# 5_-motor_driver.net
KiCad netlist of a schematic drawn in Altium Designer
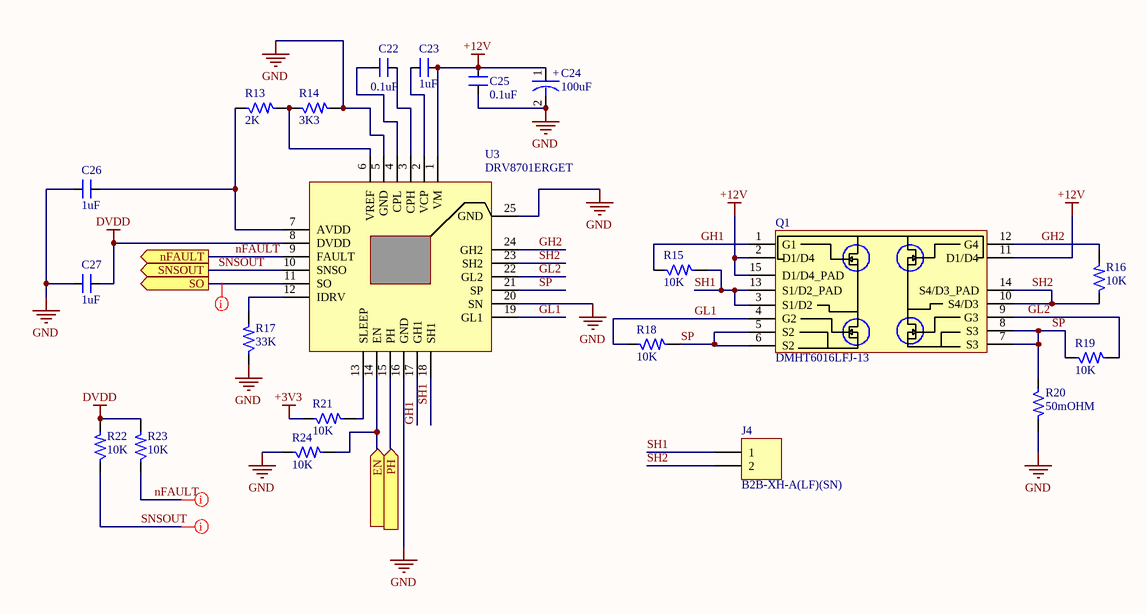
[diagram p0: [5]-motor driver.SchDoc]

(export (version "E")
  (design (tool "Eeschema 10.0.6"))
  (components
    (comp (ref "C22")
      (value "0.1uF")
      (footprint "CAP_0805")
      (description "0.1µF ±10% 50V Ceramic Capacitor X7R 0805 (2012 Metric)")
      (fields
        (field (name "MANUFACTURER") "Samsung")
        (field (name "MANUFACTURER PART NUMBER") "CL21B104KBCNNNC")
      )
      (libsource (lib "ESTEEMPCBLIB") (part "CAP_0.1uF-50V-10%-0805"))
    )
    (comp (ref "C23")
      (value "1uF")
      (footprint "CAP_0805")
      (description "1µF ±5% 50V Ceramic Capacitor X7R 0805 (2012 Metric)")
      (fields
        (field (name "MANUFACTURER") "Samsung")
        (field (name "MANUFACTURER PART NUMBER") "CC0805JKX7R9BB105")
      )
      (libsource (lib "ESTEEMPCBLIB") (part "CAP_1uF-50V-5%-0805"))
    )
    (comp (ref "C24")
      (value "100uF")
      (footprint "ACAP_P236_D305_H303_RAD")
      (description "100µF 25V Aluminum Electrolytic Capacitors Radial, Can - SMD 1000 Hrs @ 105°C")
      (fields
        (field (name "MANUFACTURER") "Nichicon")
        (field (name "MANUFACTURER PART NUMBER") "UWT1E101MCL1GS")
      )
      (libsource (lib "ESTEEMPCBLIB") (part "CAP-P_100uF-25V-20%-RAD"))
    )
    (comp (ref "C25")
      (value "0.1uF")
      (footprint "CAP_0805")
      (description "0.1µF ±10% 50V Ceramic Capacitor X7R 0805 (2012 Metric)")
      (fields
        (field (name "MANUFACTURER") "Samsung")
        (field (name "MANUFACTURER PART NUMBER") "CL21B104KBCNNNC")
      )
      (libsource (lib "ESTEEMPCBLIB") (part "CAP_0.1uF-50V-10%-0805"))
    )
    (comp (ref "C26")
      (value "1uF")
      (footprint "CAP_0805")
      (description "1µF ±5% 50V Ceramic Capacitor X7R 0805 (2012 Metric)")
      (fields
        (field (name "MANUFACTURER") "Samsung")
        (field (name "MANUFACTURER PART NUMBER") "CC0805JKX7R9BB105")
      )
      (libsource (lib "ESTEEMPCBLIB") (part "CAP_1uF-50V-5%-0805"))
    )
    (comp (ref "C27")
      (value "1uF")
      (footprint "CAP_0805")
      (description "1µF ±5% 50V Ceramic Capacitor X7R 0805 (2012 Metric)")
      (fields
        (field (name "MANUFACTURER") "Samsung")
        (field (name "MANUFACTURER PART NUMBER") "CC0805JKX7R9BB105")
      )
      (libsource (lib "ESTEEMPCBLIB") (part "CAP_1uF-50V-5%-0805"))
    )
    (comp (ref "J4")
      (value "B2B-XH-A(LF)(SN)")
      (footprint "CON2_100_B2B-XH-A_TH_ST")
      (description "2 Pins, 1 Row 2.54mm Pitch, Straight Connector, male")
      (fields (field (name "MANUFACTURER") "JST") (field (name "MATING PART NUMBER") "XHP-2"))
      (libsource (lib "ESTEEMPCBLIB") (part "CON-PLG_2X1-100-ST-TH"))
    )
    (comp (ref "Q1")
      (value "DMHT6016LFJ-13")
      (footprint "DFN5045-12_33_212_27X15_SMD_1")
      (description "Mosfet Array 4 N-Channel 14.8A (Ta) Surface Mount V-DFN5045-12")
      (fields (field (name "MANUFACTURER") "ON Semiconductor"))
      (libsource (lib "ESTEEMPCBLIB") (part "MOSFET-N_60V-14.8A-V-DFN5045-12"))
    )
    (comp (ref "R13")
      (value "2K")
      (footprint "RES_0603")
      (fields
        (field (name "MANUFACTURER") "Stackpole Electronics")
        (field (name "MANUFACTURER PART NUMBER") "RNCP0603FTD2K00")
      )
      (libsource (lib "ESTEEMPCBLIB") (part "RES_2K-0.125W-1%-0603"))
    )
    (comp (ref "R14")
      (value "3K3")
      (footprint "RES_0603")
      (description "3.3 kOhms ±1% 0.1W, 1/10W Chip Resistor 0603 (1608 Metric) Automotive AEC-Q200 Thick Film")
      (fields (field (name "MANUFACTURER") "Wilson") (field (name "MANUFACTURER PART NUMBER") "WR06X3301FTL"))
      (libsource (lib "ESTEEMPCBLIB") (part "RES_3.3K-0.1W-1%-0603"))
    )
    (comp (ref "R15")
      (value "10K")
      (footprint "RES_0603")
      (description "10 kOhms ±1% 0.1W, 1/10W Chip Resistor 0603 (1608 Metric) Automotive AEC-Q200 Thick Film")
      (fields (field (name "MANUFACTURER") "Walsin") (field (name "MANUFACTURER PART NUMBER") "WR06X1002FTL"))
      (libsource (lib "ESTEEMPCBLIB") (part "RES_10K-0.1W-1%-0603"))
    )
    (comp (ref "R16")
      (value "10K")
      (footprint "RES_0603")
      (description "10 kOhms ±1% 0.1W, 1/10W Chip Resistor 0603 (1608 Metric) Automotive AEC-Q200 Thick Film")
      (fields (field (name "MANUFACTURER") "Walsin") (field (name "MANUFACTURER PART NUMBER") "WR06X1002FTL"))
      (libsource (lib "ESTEEMPCBLIB") (part "RES_10K-0.1W-1%-0603"))
    )
    (comp (ref "R17")
      (value "33K")
      (footprint "RES_0805")
      (fields
        (field (name "MANUFACTURER") "Vishay BCcomponents")
        (field (name "MANUFACTURER PART NUMBER") "CRG0805F33K")
      )
      (libsource (lib "ESTEEMPCBLIB") (part "RES_33K-0.125W-1%-0805"))
    )
    (comp (ref "R18")
      (value "10K")
      (footprint "RES_0603")
      (description "10 kOhms ±1% 0.1W, 1/10W Chip Resistor 0603 (1608 Metric) Automotive AEC-Q200 Thick Film")
      (fields (field (name "MANUFACTURER") "Walsin") (field (name "MANUFACTURER PART NUMBER") "WR06X1002FTL"))
      (libsource (lib "ESTEEMPCBLIB") (part "RES_10K-0.1W-1%-0603"))
    )
    (comp (ref "R19")
      (value "10K")
      (footprint "RES_0603")
      (description "10 kOhms ±1% 0.1W, 1/10W Chip Resistor 0603 (1608 Metric) Automotive AEC-Q200 Thick Film")
      (fields (field (name "MANUFACTURER") "Walsin") (field (name "MANUFACTURER PART NUMBER") "WR06X1002FTL"))
      (libsource (lib "ESTEEMPCBLIB") (part "RES_10K-0.1W-1%-0603"))
    )
    (comp (ref "R20")
      (value "50mOHM")
      (footprint "RES_2512")
      (fields
        (field (name "MANUFACTURER") "Yageo")
        (field (name "MANUFACTURER PART NUMBER") "PA2512FKF7W0R05E")
      )
      (libsource (lib "ESTEEMPCBLIB") (part "RES_50mOhm-2W-1%-2512"))
    )
    (comp (ref "R21")
      (value "10K")
      (footprint "RES_0603")
      (description "10 kOhms ±1% 0.1W, 1/10W Chip Resistor 0603 (1608 Metric) Automotive AEC-Q200 Thick Film")
      (fields (field (name "MANUFACTURER") "Walsin") (field (name "MANUFACTURER PART NUMBER") "WR06X1002FTL"))
      (libsource (lib "ESTEEMPCBLIB") (part "RES_10K-0.1W-1%-0603"))
    )
    (comp (ref "R22")
      (value "10K")
      (footprint "RES_0603")
      (description "10 kOhms ±1% 0.1W, 1/10W Chip Resistor 0603 (1608 Metric) Automotive AEC-Q200 Thick Film")
      (fields (field (name "MANUFACTURER") "Walsin") (field (name "MANUFACTURER PART NUMBER") "WR06X1002FTL"))
      (libsource (lib "ESTEEMPCBLIB") (part "RES_10K-0.1W-1%-0603"))
    )
    (comp (ref "R23")
      (value "10K")
      (footprint "RES_0603")
      (description "10 kOhms ±1% 0.1W, 1/10W Chip Resistor 0603 (1608 Metric) Automotive AEC-Q200 Thick Film")
      (fields (field (name "MANUFACTURER") "Walsin") (field (name "MANUFACTURER PART NUMBER") "WR06X1002FTL"))
      (libsource (lib "ESTEEMPCBLIB") (part "RES_10K-0.1W-1%-0603"))
    )
    (comp (ref "R24")
      (value "10K")
      (footprint "RES_0603")
      (description "10 kOhms ±1% 0.1W, 1/10W Chip Resistor 0603 (1608 Metric) Automotive AEC-Q200 Thick Film")
      (fields (field (name "MANUFACTURER") "Walsin") (field (name "MANUFACTURER PART NUMBER") "WR06X1002FTL"))
      (libsource (lib "ESTEEMPCBLIB") (part "RES_10K-0.1W-1%-0603"))
    )
    (comp (ref "U3")
      (value "DRV8701ERGET")
      (footprint "VFQFN24_19.6_196_12X32_SMD_1")
      (description "Motor Driver Power MOSFET Parallel 24-VQFN (4x4)")
      (fields (field (name "MANUFACTURER") "Texas Instruments"))
      (libsource (lib "ESTEEMPCBLIB") (part "IC_DRV8701ERGET"))
    )
  )
  (nets
    (net (code "1") (name "+3V3") (class "Default")
      (node (ref "R21") (pin "1") (pinfunction "1_1") (pintype "passive"))
    )
    (net (code "2") (name "+12V") (class "Default")
      (node (ref "C23") (pin "2") (pinfunction "2_2") (pintype "passive"))
      (node (ref "C24") (pin "1") (pinfunction "1_1") (pintype "passive"))
      (node (ref "C25") (pin "2") (pinfunction "2_2") (pintype "passive"))
      (node (ref "Q1") (pin "11") (pinfunction "D1/D4_11") (pintype "passive"))
      (node (ref "Q1") (pin "15") (pinfunction "D1/D4_PAD_15") (pintype "passive"))
      (node (ref "Q1") (pin "2") (pinfunction "D1/D4_2") (pintype "passive"))
      (node (ref "U3") (pin "1") (pinfunction "VM_1") (pintype "passive"))
    )
    (net (code "3") (name "/EN") (class "Default")
      (node (ref "R24") (pin "2") (pinfunction "2_2") (pintype "passive"))
      (node (ref "U3") (pin "14") (pinfunction "EN_14") (pintype "passive"))
    )
    (net (code "4") (name "/GH1") (class "Default")
      (node (ref "Q1") (pin "1") (pinfunction "G1_1") (pintype "passive"))
      (node (ref "R15") (pin "1") (pinfunction "1_1") (pintype "passive"))
      (node (ref "U3") (pin "17") (pinfunction "GH1_17") (pintype "passive"))
    )
    (net (code "5") (name "/GH2") (class "Default")
      (node (ref "Q1") (pin "12") (pinfunction "G4_12") (pintype "passive"))
      (node (ref "R16") (pin "2") (pinfunction "2_2") (pintype "passive"))
      (node (ref "U3") (pin "24") (pinfunction "GH2_24") (pintype "passive"))
    )
    (net (code "6") (name "/GL1") (class "Default")
      (node (ref "Q1") (pin "4") (pinfunction "G2_4") (pintype "passive"))
      (node (ref "R18") (pin "1") (pinfunction "1_1") (pintype "passive"))
      (node (ref "U3") (pin "19") (pinfunction "GL1_19") (pintype "passive"))
    )
    (net (code "7") (name "/GL2") (class "Default")
      (node (ref "Q1") (pin "9") (pinfunction "G3_9") (pintype "passive"))
      (node (ref "R19") (pin "2") (pinfunction "2_2") (pintype "passive"))
      (node (ref "U3") (pin "22") (pinfunction "GL2_22") (pintype "passive"))
    )
    (net (code "8") (name "/PH") (class "Default")
      (node (ref "U3") (pin "15") (pinfunction "PH_15") (pintype "passive"))
    )
    (net (code "9") (name "/SH1") (class "Default")
      (node (ref "J4") (pin "1") (pinfunction "1_1") (pintype "passive"))
      (node (ref "Q1") (pin "13") (pinfunction "S1/D2_PAD_13") (pintype "passive"))
      (node (ref "Q1") (pin "3") (pinfunction "S1/D2_3") (pintype "passive"))
      (node (ref "R15") (pin "2") (pinfunction "2_2") (pintype "passive"))
      (node (ref "U3") (pin "18") (pinfunction "SH1_18") (pintype "passive"))
    )
    (net (code "10") (name "/SH2") (class "Default")
      (node (ref "J4") (pin "2") (pinfunction "2_2") (pintype "passive"))
      (node (ref "Q1") (pin "10") (pinfunction "S4/D3_10") (pintype "passive"))
      (node (ref "Q1") (pin "14") (pinfunction "S4/D3_PAD_14") (pintype "passive"))
      (node (ref "R16") (pin "1") (pinfunction "1_1") (pintype "passive"))
      (node (ref "U3") (pin "23") (pinfunction "SH2_23") (pintype "passive"))
    )
    (net (code "11") (name "/SNSOUT") (class "Default")
      (node (ref "R22") (pin "1") (pinfunction "1_1") (pintype "passive"))
      (node (ref "U3") (pin "10") (pinfunction "SNSO_10") (pintype "passive"))
    )
    (net (code "12") (name "/SO") (class "Default")
      (node (ref "U3") (pin "11") (pinfunction "SO_11") (pintype "passive"))
    )
    (net (code "13") (name "/SP") (class "Default")
      (node (ref "Q1") (pin "5") (pinfunction "S2_5") (pintype "passive"))
      (node (ref "Q1") (pin "6") (pinfunction "S2_6") (pintype "passive"))
      (node (ref "Q1") (pin "7") (pinfunction "S3_7") (pintype "passive"))
      (node (ref "Q1") (pin "8") (pinfunction "S3_8") (pintype "passive"))
      (node (ref "R18") (pin "2") (pinfunction "2_2") (pintype "passive"))
      (node (ref "R19") (pin "1") (pinfunction "1_1") (pintype "passive"))
      (node (ref "R20") (pin "1") (pinfunction "1_1") (pintype "passive"))
      (node (ref "U3") (pin "21") (pinfunction "SP_21") (pintype "passive"))
    )
    (net (code "14") (name "/nFAULT") (class "Default")
      (node (ref "R23") (pin "1") (pinfunction "1_1") (pintype "passive"))
      (node (ref "U3") (pin "9") (pinfunction "FAULT_9") (pintype "passive"))
    )
    (net (code "15") (name "DVDD") (class "Default")
      (node (ref "C27") (pin "2") (pinfunction "2_2") (pintype "passive"))
      (node (ref "R22") (pin "2") (pinfunction "2_2") (pintype "passive"))
      (node (ref "R23") (pin "2") (pinfunction "2_2") (pintype "passive"))
      (node (ref "U3") (pin "8") (pinfunction "DVDD_8") (pintype "passive"))
    )
    (net (code "16") (name "GND") (class "Default")
      (node (ref "C24") (pin "2") (pinfunction "2_2") (pintype "passive"))
      (node (ref "C25") (pin "1") (pinfunction "1_1") (pintype "passive"))
      (node (ref "C26") (pin "1") (pinfunction "1_1") (pintype "passive"))
      (node (ref "C27") (pin "1") (pinfunction "1_1") (pintype "passive"))
      (node (ref "R14") (pin "2") (pinfunction "2_2") (pintype "passive"))
      (node (ref "R17") (pin "1") (pinfunction "1_1") (pintype "passive"))
      (node (ref "R20") (pin "2") (pinfunction "2_2") (pintype "passive"))
      (node (ref "R24") (pin "1") (pinfunction "1_1") (pintype "passive"))
      (node (ref "U3") (pin "16") (pinfunction "GND_16") (pintype "passive"))
      (node (ref "U3") (pin "20") (pinfunction "SN_20") (pintype "passive"))
      (node (ref "U3") (pin "25") (pinfunction "GND_25") (pintype "passive"))
      (node (ref "U3") (pin "5") (pinfunction "GND_5") (pintype "passive"))
    )
    (net (code "17") (name "Net-(U3-AVDD)") (class "Default")
      (node (ref "C26") (pin "2") (pinfunction "2_2") (pintype "passive"))
      (node (ref "R13") (pin "1") (pinfunction "1_1") (pintype "passive"))
      (node (ref "U3") (pin "7") (pinfunction "AVDD_7") (pintype "passive"))
    )
    (net (code "18") (name "Net-(U3-CPH)") (class "Default")
      (node (ref "C22") (pin "1") (pinfunction "1_1") (pintype "passive"))
      (node (ref "U3") (pin "3") (pinfunction "CPH_3") (pintype "passive"))
    )
    (net (code "19") (name "Net-(U3-CPL)") (class "Default")
      (node (ref "C22") (pin "2") (pinfunction "2_2") (pintype "passive"))
      (node (ref "U3") (pin "4") (pinfunction "CPL_4") (pintype "passive"))
    )
    (net (code "20") (name "Net-(U3-IDRV)") (class "Default")
      (node (ref "R17") (pin "2") (pinfunction "2_2") (pintype "passive"))
      (node (ref "U3") (pin "12") (pinfunction "IDRV_12") (pintype "passive"))
    )
    (net (code "21") (name "Net-(U3-SLEEP)") (class "Default")
      (node (ref "R21") (pin "2") (pinfunction "2_2") (pintype "passive"))
      (node (ref "U3") (pin "13") (pinfunction "SLEEP_13") (pintype "passive"))
    )
    (net (code "22") (name "Net-(U3-VCP)") (class "Default")
      (node (ref "C23") (pin "1") (pinfunction "1_1") (pintype "passive"))
      (node (ref "U3") (pin "2") (pinfunction "VCP_2") (pintype "passive"))
    )
    (net (code "23") (name "Net-(U3-VREF)") (class "Default")
      (node (ref "R13") (pin "2") (pinfunction "2_2") (pintype "passive"))
      (node (ref "R14") (pin "1") (pinfunction "1_1") (pintype "passive"))
      (node (ref "U3") (pin "6") (pinfunction "VREF_6") (pintype "passive"))
    )
  )
)
